# ProxSensorType2_Recieve.net
KiCad netlist of a schematic drawn in Altium Designer
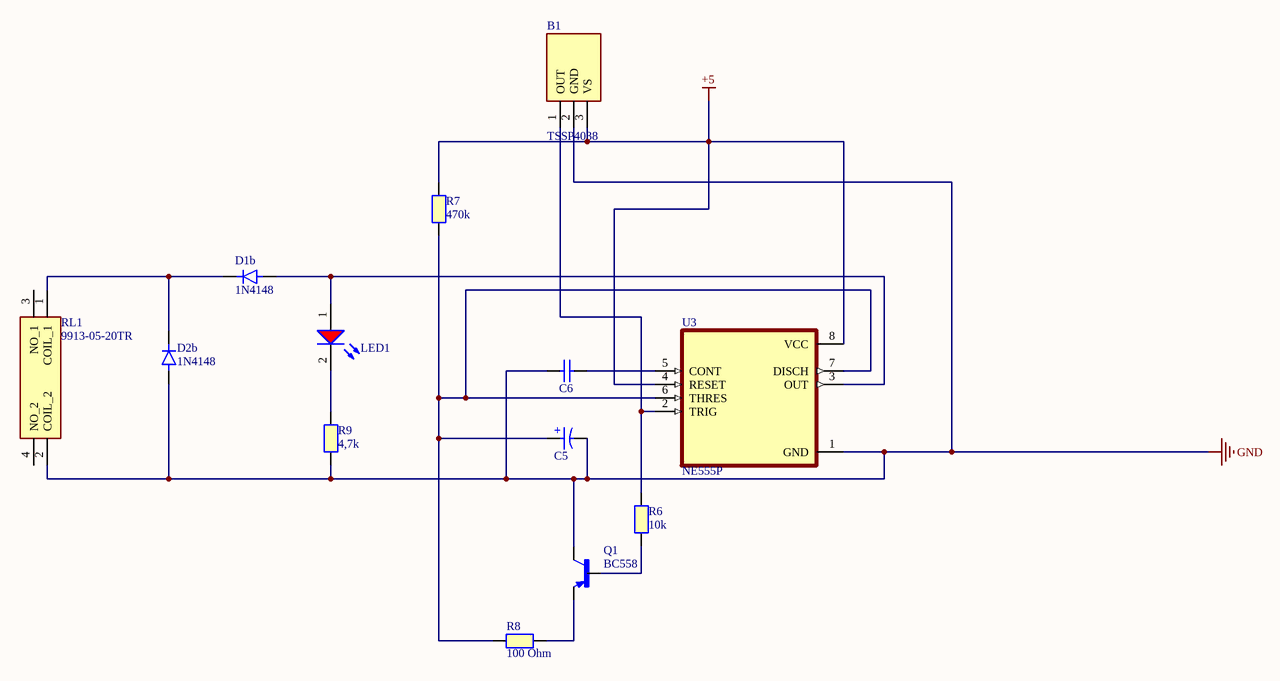
[diagram p0: ProxSensorType2_Recieve.SchDoc]

(export (version "E")
  (design (tool "Eeschema 10.0.6"))
  (components
    (comp (ref "B1")
      (value "TSSP4038")
      (footprint "TSSP4038")
      (fields (field (name "MOUSER PART NUMBER") "782-TSSP4038"))
      (libsource (lib "Sensor_1") (part "TSSP4038"))
    )
    (comp (ref "C5")
      (value "4,7µF")
      (footprint "WCAP-ATG8_D5H11")
      (description "WCAP-ATG8 Aluminum Electrolytic Capacitor, Radial, THT, D5 x H11mm, 100µF, 10V")
      (fields
        (field (name "MANUFACTURER PART NUMBER") "860010272005")
        (field (name "MANUFACTURER") "Wurth Elektronik")
      )
      (libsource (lib "Sensor_1") (part "860010272005"))
    )
    (comp (ref "C6")
      (value "0,01uF")
      (footprint "WCAP-CSGP_0805_L2W1.25H0.8_Wave")
      (description "WCAP-CSGP Multilayer Ceramic Chip Capacitor, General Purpose, size 0201, NP0 Class I, 22pF, 25VDC")
      (fields
        (field (name "MANUFACTURER PART NUMBER") "885012004008")
        (field (name "MANUFACTURER") "Wurth Elektronik")
      )
      (libsource (lib "Sensor_1") (part "885012004008"))
    )
    (comp (ref "D1b")
      (value "1N4148")
      (footprint "DIOAD829W49L456D191")
      (description "Diode Standard 75V 200mA Surface Mount SOD-523F")
      (fields (field (name "MF") "ON Semiconductor"))
      (libsource (lib "Sensor_1") (part "1N4148"))
    )
    (comp (ref "D2b")
      (value "1N4148")
      (footprint "DIOAD829W49L456D191")
      (description "Diode Standard 75V 200mA Surface Mount SOD-523F")
      (fields (field (name "MF") "ON Semiconductor"))
      (libsource (lib "Sensor_1") (part "1N4148"))
    )
    (comp (ref "LED1")
      (value "Super Red, 2.1V, 40°")
      (footprint "WL-TMRC_D5.9H8.7")
      (description "WL-TMRC Mono-color Round Color, THT, D5.9 x H8.7mm, Super Red, 2.1V, 40°")
      (fields
        (field (name "MANUFACTURER PART NUMBER") "151051SS04000")
        (field (name "MANUFACTURER") "Wurth Elektronik")
      )
      (libsource (lib "Sensor_1") (part "LED_151051SS04000"))
    )
    (comp (ref "Q1")
      (value "BC558")
      (description "Bipolar (BJT) Transistor PNP 30 V 100 mA 360MHz 625 mW Through Hole TO-92 (TO-226)")
      (fields (field (name "MF") "ON"))
      (libsource (lib "Sensor_1") (part "BC558"))
    )
    (comp (ref "R6")
      (value "10k")
      (footprint "RESC2012X50N")
      (description "4,7k Resistor 0805")
      (fields (field (name "PART NUMBER") "TNPW080510K0BETA") (field (name "MANUFACTURER") "Vishay Dale"))
      (libsource (lib "Sensor_1") (part "RESISTOR 0805"))
    )
    (comp (ref "R7")
      (value "470k")
      (footprint "RESC2012X50N")
      (description "4,7k Resistor 0805")
      (fields (field (name "PART NUMBER") "TNPW080510K0BETA") (field (name "MANUFACTURER") "Vishay Dale"))
      (libsource (lib "Sensor_1") (part "RESISTOR 0805"))
    )
    (comp (ref "R8")
      (value "100 Ohm")
      (footprint "RESC2012X50N")
      (description "4,7k Resistor 0805")
      (fields (field (name "PART NUMBER") "TNPW080510K0BETA") (field (name "MANUFACTURER") "Vishay Dale"))
      (libsource (lib "") (part "RESISTOR 0805_1"))
    )
    (comp (ref "R9")
      (value "4,7k")
      (footprint "RESC2012X50N")
      (description "4,7k Resistor 0805")
      (fields (field (name "PART NUMBER") "TNPW080510K0BETA") (field (name "MANUFACTURER") "Vishay Dale"))
      (libsource (lib "Sensor_1") (part "RESISTOR 0805"))
    )
    (comp (ref "RL1")
      (value "9913-05-20TR")
      (footprint "99130520TR")
      (description "RELAY STANDARD REED, 5V, 200 OHMS, J FORM, TR. / TAPE-REEL")
      (fields (field (name "MOUSER PART NUMBER") "816-9913-05-20TR"))
      (libsource (lib "Sensor_1") (part "9913-05-20TR"))
    )
    (comp (ref "U3")
      (value "NE555P")
      (footprint "Sensor_1:DIP794W45P254L959H508Q8")
      (libsource (lib "Sensor_1") (part "NE555P"))
    )
  )
  (nets
    (net (code "1") (name "+5") (class "Default")
      (node (ref "B1") (pin "3") (pinfunction "VS_3") (pintype "passive"))
      (node (ref "R7") (pin "2") (pinfunction "2_2") (pintype "passive"))
      (node (ref "U3") (pin "4") (pinfunction "RESET_4") (pintype "input"))
      (node (ref "U3") (pin "8") (pinfunction "VCC_8") (pintype "power_in"))
    )
    (net (code "2") (name "GND") (class "Default")
      (node (ref "B1") (pin "2") (pinfunction "GND_2") (pintype "passive"))
      (node (ref "C5") (pin "2") (pinfunction "N_2") (pintype "passive"))
      (node (ref "C6") (pin "1") (pinfunction "1_1") (pintype "passive"))
      (node (ref "D2b") (pin "A") (pinfunction "A_A") (pintype "passive"))
      (node (ref "Q1") (pin "1") (pinfunction "C_1") (pintype "passive"))
      (node (ref "R9") (pin "1") (pinfunction "1_1") (pintype "passive"))
      (node (ref "RL1") (pin "2") (pinfunction "COIL_2_2") (pintype "passive"))
      (node (ref "U3") (pin "1") (pinfunction "GND_1") (pintype "power_in"))
    )
    (net (code "3") (name "Net-(B1-OUT)") (class "Default")
      (node (ref "B1") (pin "1") (pinfunction "OUT_1") (pintype "passive"))
      (node (ref "R6") (pin "2") (pinfunction "2_2") (pintype "passive"))
      (node (ref "U3") (pin "2") (pinfunction "TRIG_2") (pintype "input"))
    )
    (net (code "4") (name "Net-(C5-P)") (class "Default")
      (node (ref "C5") (pin "1") (pinfunction "P_1") (pintype "passive"))
      (node (ref "R7") (pin "1") (pinfunction "1_1") (pintype "passive"))
      (node (ref "R8") (pin "1") (pinfunction "1_1") (pintype "passive"))
      (node (ref "U3") (pin "6") (pinfunction "THRES_6") (pintype "input"))
      (node (ref "U3") (pin "7") (pinfunction "DISCH_7") (pintype "output"))
    )
    (net (code "5") (name "Net-(LED1-A)") (class "Default")
      (node (ref "D1b") (pin "A") (pinfunction "A_A") (pintype "passive"))
      (node (ref "LED1") (pin "1") (pinfunction "A_1") (pintype "passive"))
      (node (ref "U3") (pin "3") (pinfunction "OUT_3") (pintype "output"))
    )
    (net (code "6") (name "Net-(LED1-K)") (class "Default")
      (node (ref "LED1") (pin "2") (pinfunction "K_2") (pintype "passive"))
      (node (ref "R9") (pin "2") (pinfunction "2_2") (pintype "passive"))
    )
    (net (code "7") (name "Net-(Q1-B)") (class "Default")
      (node (ref "Q1") (pin "2") (pinfunction "B_2") (pintype "passive"))
      (node (ref "R6") (pin "1") (pinfunction "1_1") (pintype "passive"))
    )
    (net (code "8") (name "Net-(Q1-E)") (class "Default")
      (node (ref "Q1") (pin "3") (pinfunction "E_3") (pintype "passive"))
      (node (ref "R8") (pin "2") (pinfunction "2_2") (pintype "passive"))
    )
    (net (code "9") (name "Net-(RL1-COIL_1)") (class "Default")
      (node (ref "D1b") (pin "C") (pinfunction "C_C") (pintype "passive"))
      (node (ref "D2b") (pin "C") (pinfunction "C_C") (pintype "passive"))
      (node (ref "RL1") (pin "1") (pinfunction "COIL_1_1") (pintype "passive"))
    )
    (net (code "10") (name "Net-(U3-CONT)") (class "Default")
      (node (ref "C6") (pin "2") (pinfunction "2_2") (pintype "passive"))
      (node (ref "U3") (pin "5") (pinfunction "CONT_5") (pintype "input"))
    )
    (net (code "11") (name "unconnected-(RL1-NO_1-Pad3)") (class "Default")
      (node (ref "RL1") (pin "3") (pinfunction "NO_1_3") (pintype "passive"))
    )
    (net (code "12") (name "unconnected-(RL1-NO_2-Pad4)") (class "Default")
      (node (ref "RL1") (pin "4") (pinfunction "NO_2_4") (pintype "passive"))
    )
  )
)
